# DS132-1_2-B.net
KiCad netlist of a schematic drawn in Altium Designer
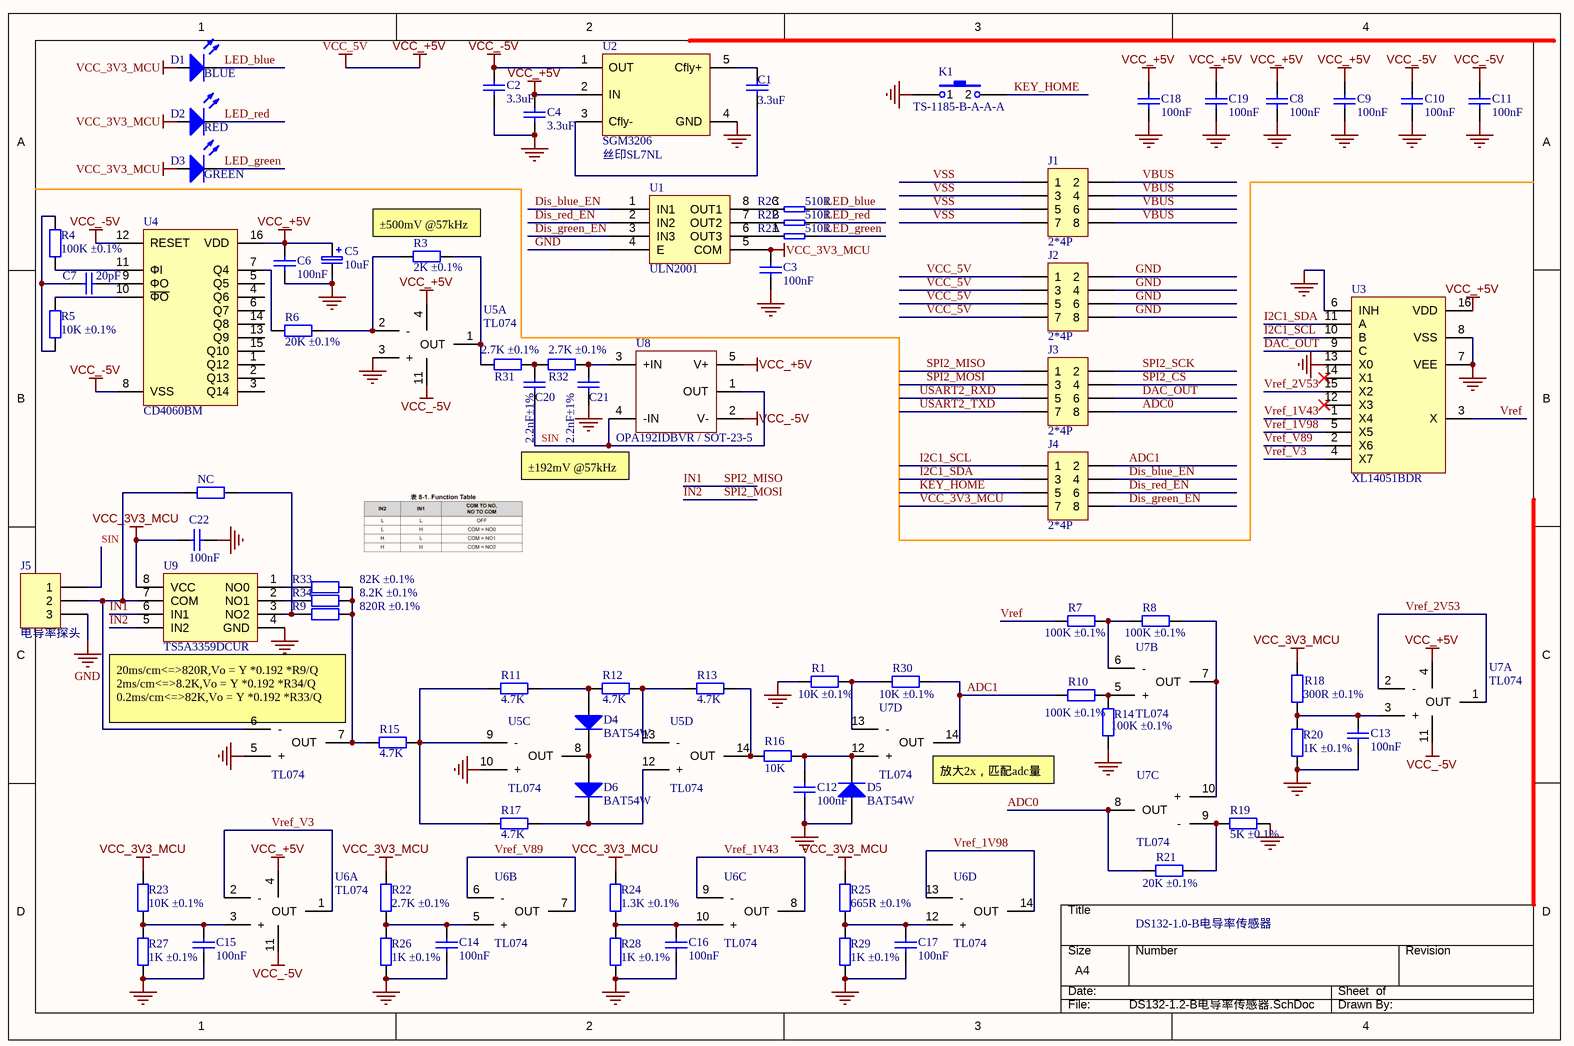
[diagram p0: DS132-1.2-B电导率传感器.SchDoc]

(export (version "E")
  (design (tool "Eeschema 10.0.6"))
  (components
    (comp (ref "C1")
      (value "3.3uF")
      (footprint "0603CAP")
      (description "贴片电容")
      (fields (field (name "Comment") "MLCC 3.3uF 50V ±10％ 0603"))
      (libsource (lib "AD_SCH") (part "MLCC 3.3uF 50V ±10％ 0603"))
    )
    (comp (ref "C2")
      (value "3.3uF")
      (footprint "0603CAP")
      (description "贴片电容")
      (libsource (lib "AD_SCH") (part "MLCC 3.3uF 50V ±10％ 0603"))
    )
    (comp (ref "C3")
      (value "100nF")
      (footprint "0603CAP")
      (description "贴片电容")
      (libsource (lib "AD_SCH") (part "MLCC 100nF 50V ±10％ 0603"))
    )
    (comp (ref "C4")
      (value "3.3uF")
      (footprint "0603CAP")
      (description "贴片电容")
      (fields (field (name "Comment") "MLCC 3.3uF 50V ±10％ 0603"))
      (libsource (lib "AD_SCH") (part "MLCC 3.3uF 50V ±10％ 0603"))
    )
    (comp (ref "C5")
      (value "10uF")
      (footprint "AVX_3216-18(1206)_SMD")
      (description "钽电容")
      (fields (field (name "Comment") "AVX_10uF/16V ±10％(C106)"))
      (libsource (lib "AD_SCH") (part "AVX_10uF/16V ±10％(C106)"))
    )
    (comp (ref "C6")
      (value "100nF")
      (footprint "0603CAP")
      (description "贴片电容")
      (fields (field (name "Comment") "SMDCAP00013"))
      (libsource (lib "AD_SCH") (part "MLCC 100nF 50V ±10％ 0603"))
    )
    (comp (ref "C7")
      (value "20pF")
      (footprint "0603CAP")
      (description "贴片电容")
      (fields (field (name "Comment") "SMDCAP00002"))
      (libsource (lib "AD_SCH") (part "MLCC 20pF 50V ±10％ 0603"))
    )
    (comp (ref "C8")
      (value "100nF")
      (footprint "0603CAP")
      (description "贴片电容")
      (libsource (lib "AD_SCH") (part "MLCC 100nF 50V ±10％ 0603"))
    )
    (comp (ref "C9")
      (value "100nF")
      (footprint "0603CAP")
      (description "贴片电容")
      (libsource (lib "AD_SCH") (part "MLCC 100nF 50V ±10％ 0603"))
    )
    (comp (ref "C10")
      (value "100nF")
      (footprint "0603CAP")
      (description "贴片电容")
      (libsource (lib "AD_SCH") (part "MLCC 100nF 50V ±10％ 0603"))
    )
    (comp (ref "C11")
      (value "100nF")
      (footprint "0603CAP")
      (description "贴片电容")
      (libsource (lib "AD_SCH") (part "MLCC 100nF 50V ±10％ 0603"))
    )
    (comp (ref "C12")
      (value "100nF")
      (footprint "0603CAP")
      (description "贴片电容")
      (libsource (lib "AD_SCH") (part "MLCC 100nF 50V ±10％ 0603"))
    )
    (comp (ref "C13")
      (value "100nF")
      (footprint "0603CAP")
      (description "贴片电容")
      (libsource (lib "AD_SCH") (part "MLCC 100nF 50V ±10％ 0603"))
    )
    (comp (ref "C14")
      (value "100nF")
      (footprint "0603CAP")
      (description "贴片电容")
      (libsource (lib "AD_SCH") (part "MLCC 100nF 50V ±10％ 0603"))
    )
    (comp (ref "C15")
      (value "100nF")
      (footprint "0603CAP")
      (description "贴片电容")
      (libsource (lib "AD_SCH") (part "MLCC 100nF 50V ±10％ 0603"))
    )
    (comp (ref "C16")
      (value "100nF")
      (footprint "0603CAP")
      (description "贴片电容")
      (libsource (lib "AD_SCH") (part "MLCC 100nF 50V ±10％ 0603"))
    )
    (comp (ref "C17")
      (value "100nF")
      (footprint "0603CAP")
      (description "贴片电容")
      (libsource (lib "AD_SCH") (part "MLCC 100nF 50V ±10％ 0603"))
    )
    (comp (ref "C18")
      (value "100nF")
      (footprint "0603CAP")
      (description "贴片电容")
      (libsource (lib "AD_SCH") (part "MLCC 100nF 50V ±10％ 0603"))
    )
    (comp (ref "C19")
      (value "100nF")
      (footprint "0603CAP")
      (description "贴片电容")
      (libsource (lib "AD_SCH") (part "MLCC 100nF 50V ±10％ 0603"))
    )
    (comp (ref "C20")
      (value "2.2nF±1%")
      (footprint "0603CAP")
      (description "贴片电容")
      (fields (field (name "Comment") "MLCC 2.2nF 50V ±1％ 0603"))
      (libsource (lib "AD_SCH") (part "MLCC 2.2nF 50V ±1％ 0603"))
    )
    (comp (ref "C21")
      (value "2.2nF±1%")
      (footprint "0603CAP")
      (description "贴片电容")
      (fields (field (name "Comment") "MLCC 2.2nF 50V ±1％ 0603"))
      (libsource (lib "AD_SCH") (part "MLCC 2.2nF 50V ±1％ 0603"))
    )
    (comp (ref "C22")
      (value "100nF")
      (footprint "0603CAP")
      (description "贴片电容")
      (libsource (lib "AD_SCH") (part "MLCC 100nF 50V ±10％ 0603"))
    )
    (comp (ref "D1")
      (value "BLUE")
      (footprint "LED_0805")
      (description "贴片LED")
      (fields (field (name "Comment") "SMDLED00010"))
      (libsource (lib "AD_SCH") (part "Chip 蓝色LED 0805"))
    )
    (comp (ref "D2")
      (value "RED")
      (footprint "LED_0805")
      (description "贴片LED")
      (fields (field (name "Comment") "SMDLED00003"))
      (libsource (lib "AD_SCH") (part "Chip 红色LED 0805"))
    )
    (comp (ref "D3")
      (value "GREEN")
      (footprint "LED_0805")
      (description "贴片LED")
      (fields (field (name "Comment") "Chip 翠绿LED 0805"))
      (libsource (lib "AD_SCH") (part "Chip 翠绿LED 0805"))
    )
    (comp (ref "D4") (value "BAT54W") (footprint "SOD-123") (libsource (lib "AD_SCH") (part "BAT54W")))
    (comp (ref "D5") (value "BAT54W") (footprint "SOD-123") (libsource (lib "AD_SCH") (part "BAT54W")))
    (comp (ref "D6") (value "BAT54W") (footprint "SOD-123") (libsource (lib "AD_SCH") (part "BAT54W")))
    (comp (ref "J1")
      (value "2*4P")
      (footprint "X1321WVS-2x04J-C40D53")
      (description "双排针2x4P 立贴 1.27mm")
      (fields (field (name "Comment") "X1321WVS-2x04J-C40D53"))
      (libsource (lib "AD_SCH") (part "X1321WVS-2x04J-C40D53"))
    )
    (comp (ref "J2")
      (value "2*4P")
      (footprint "X1321WVS-2x04J-C40D53")
      (description "双排针2x4P 立贴 1.27mm")
      (fields (field (name "Comment") "X1321WVS-2x04J-C40D53"))
      (libsource (lib "AD_SCH") (part "X1321WVS-2x04J-C40D53"))
    )
    (comp (ref "J3")
      (value "2*4P")
      (footprint "X1321WVS-2x04J-C40D53")
      (description "双排针2x4P 立贴 1.27mm")
      (fields (field (name "Comment") "X1321WVS-2x04J-C40D53"))
      (libsource (lib "AD_SCH") (part "X1321WVS-2x04J-C40D53"))
    )
    (comp (ref "J4")
      (value "2*4P")
      (footprint "X1321WVS-2x04J-C40D53")
      (description "双排针2x4P 立贴 1.27mm")
      (fields (field (name "Comment") "X1321WVS-2x04J-C40D53"))
      (libsource (lib "AD_SCH") (part "X1321WVS-2x04J-C40D53"))
    )
    (comp (ref "J5")
      (value "电导率探头")
      (footprint "SIP3")
      (description "单排直针")
      (fields (field (name "Comment") "SL000000042"))
      (libsource (lib "AD_SCH") (part "DIP3 单排直针 间距2.54mm 针长11mm 铜"))
    )
    (comp (ref "K1")
      (value "TS-1185-B-A-A-A")
      (footprint "KEY_TS-1185-x-A-A-A")
      (description "轻触开关")
      (libsource (lib "AD_SCH") (part "TS-1185-B-A-A-A"))
    )
    (comp (ref "NC")
      (value "Chip 0R 1/16W ±1％ 0603")
      (footprint "0603RES")
      (description "贴片电阻")
      (libsource (lib "AD_SCH") (part "Chip 0R 1/16W ±1％ 0603"))
    )
    (comp (ref "R1")
      (value "10K ±0.1%")
      (footprint "0603RES")
      (fields (field (name "Comment") "Chip 10K 1/10W ±0.1％ 0603"))
      (libsource (lib "") (part "Chip 10K 1/10W ±0.1％ 0603_1"))
    )
    (comp (ref "R2")
      (value "510R")
      (footprint "0603RES_Pack4")
      (description "贴片排阻")
      (fields (field (name "Comment") "SMDRES05003"))
      (libsource (lib "AD_SCH") (part "Chip R*4 510R 1/16W ±5％ 0603"))
    )
    (comp (ref "R3")
      (value "2K ±0.1%")
      (footprint "0603RES")
      (fields (field (name "Comment") "Chip 2K 1/10W ±0.1％ 0603"))
      (libsource (lib "AD_SCH") (part "Chip 2K 1/10W ±0.1％ 0603"))
    )
    (comp (ref "R4")
      (value "100K ±0.1%")
      (footprint "0603RES")
      (libsource (lib "") (part "Chip 100K 1/10W ±0.1％ 0603_1"))
    )
    (comp (ref "R5")
      (value "10K ±0.1%")
      (footprint "0603RES")
      (fields (field (name "Comment") "Chip 10K 1/10W ±0.1％ 0603"))
      (libsource (lib "AD_SCH") (part "Chip 10K 1/10W ±0.1％ 0603"))
    )
    (comp (ref "R6")
      (value "20K ±0.1%")
      (footprint "0603RES")
      (fields (field (name "Comment") "Chip 20K 1/10W ±0.1％ 0603"))
      (libsource (lib "AD_SCH") (part "Chip 20K 1/10W ±0.1％ 0603"))
    )
    (comp (ref "R7")
      (value "100K ±0.1%")
      (footprint "0603RES")
      (fields (field (name "Comment") "Chip 100K 1/10W ±0.1％ 0603"))
      (libsource (lib "") (part "Chip 100K 1/10W ±0.1％ 0603_2"))
    )
    (comp (ref "R8")
      (value "100K ±0.1%")
      (footprint "0603RES")
      (fields (field (name "Comment") "Chip 100K 1/10W ±0.1％ 0603"))
      (libsource (lib "AD_SCH") (part "Chip 100K 1/10W ±0.1％ 0603"))
    )
    (comp (ref "R9")
      (value "820R ±0.1%")
      (footprint "0603RES")
      (fields (field (name "Comment") "Chip 820R 1/10W ±0.1％ 0603"))
      (libsource (lib "AD_SCH") (part "Chip 820R 1/10W ±0.1％ 0603"))
    )
    (comp (ref "R10")
      (value "100K ±0.1%")
      (footprint "0603RES")
      (fields (field (name "Comment") "Chip 100K 1/10W ±0.1％ 0603"))
      (libsource (lib "") (part "Chip 100K 1/10W ±0.1％ 0603_2"))
    )
    (comp (ref "R11")
      (value "4.7K")
      (footprint "0603RES")
      (description "贴片电阻")
      (fields (field (name "Comment") "SMDRES00047"))
      (libsource (lib "AD_SCH") (part "Chip 4.7K 1/10W ±1％ 0603"))
    )
    (comp (ref "R12")
      (value "4.7K")
      (footprint "0603RES")
      (description "贴片电阻")
      (fields (field (name "Comment") "SMDRES00047"))
      (libsource (lib "AD_SCH") (part "Chip 4.7K 1/10W ±1％ 0603"))
    )
    (comp (ref "R13")
      (value "4.7K")
      (footprint "0603RES")
      (description "贴片电阻")
      (fields (field (name "Comment") "SMDRES00047"))
      (libsource (lib "AD_SCH") (part "Chip 4.7K 1/10W ±1％ 0603"))
    )
    (comp (ref "R14")
      (value "100K ±0.1%")
      (footprint "0603RES")
      (fields (field (name "Comment") "Chip 100K 1/10W ±0.1％ 0603"))
      (libsource (lib "") (part "Chip 100K 1/10W ±0.1％ 0603_1"))
    )
    (comp (ref "R15")
      (value "4.7K")
      (footprint "0603RES")
      (description "贴片电阻")
      (fields (field (name "Comment") "SMDRES00047"))
      (libsource (lib "AD_SCH") (part "Chip 4.7K 1/10W ±1％ 0603"))
    )
    (comp (ref "R16")
      (value "10K")
      (footprint "0603RES")
      (description "贴片电阻")
      (fields (field (name "Comment") "Chip 10K 1/16W ±1％ 0603"))
      (libsource (lib "AD_SCH") (part "Chip 10K 1/16W ±1％ 0603"))
    )
    (comp (ref "R17")
      (value "4.7K")
      (footprint "0603RES")
      (description "贴片电阻")
      (fields (field (name "Comment") "SMDRES00047"))
      (libsource (lib "AD_SCH") (part "Chip 4.7K 1/10W ±1％ 0603"))
    )
    (comp (ref "R18")
      (value "300R ±0.1%")
      (footprint "0603RES")
      (libsource (lib "AD_SCH") (part "Chip 300R 1/10W ±0.1％ 0603"))
    )
    (comp (ref "R19")
      (value "5K ±0.1%")
      (footprint "0603RES")
      (fields (field (name "Comment") "Chip 5K 1/10W ±0.1％ 0603"))
      (libsource (lib "AD_SCH") (part "Chip 5K 1/10W ±0.1％ 0603"))
    )
    (comp (ref "R20")
      (value "1K ±0.1%")
      (footprint "0603RES")
      (fields (field (name "Comment") "Chip 1K 1/10W ±0.1％ 0603"))
      (libsource (lib "AD_SCH") (part "Chip 1K 1/10W ±0.1％ 0603"))
    )
    (comp (ref "R21")
      (value "20K ±0.1%")
      (footprint "0603RES")
      (fields (field (name "Comment") "Chip 20K 1/10W ±0.1％ 0603"))
      (libsource (lib "AD_SCH") (part "Chip 20K 1/10W ±0.1％ 0603"))
    )
    (comp (ref "R22")
      (value "2.7K ±0.1%")
      (footprint "0603RES")
      (fields (field (name "Comment") "Chip 2.7K 1/10W ±0.1％ 0603"))
      (libsource (lib "") (part "Chip 2.7K 1/10W ±0.1％ 0603_1"))
    )
    (comp (ref "R23")
      (value "10K ±0.1%")
      (footprint "0603RES")
      (fields (field (name "Comment") "Chip 10K 1/10W ±0.1％ 0603"))
      (libsource (lib "AD_SCH") (part "Chip 10K 1/10W ±0.1％ 0603"))
    )
    (comp (ref "R24")
      (value "1.3K ±0.1%")
      (footprint "0603RES")
      (fields (field (name "Comment") "Chip 1.3K 1/10W ±0.1％ 0603"))
      (libsource (lib "AD_SCH") (part "Chip 1.3K 1/10W ±0.1％ 0603"))
    )
    (comp (ref "R25")
      (value "665R ±0.1%")
      (footprint "0603RES")
      (fields (field (name "Comment") "Chip 665R 1/10W ±0.1％ 0603"))
      (libsource (lib "AD_SCH") (part "Chip 665R 1/10W ±0.1％ 0603"))
    )
    (comp (ref "R26")
      (value "1K ±0.1%")
      (footprint "0603RES")
      (fields (field (name "Comment") "Chip 1K 1/10W ±0.1％ 0603"))
      (libsource (lib "AD_SCH") (part "Chip 1K 1/10W ±0.1％ 0603"))
    )
    (comp (ref "R27")
      (value "1K ±0.1%")
      (footprint "0603RES")
      (fields (field (name "Comment") "Chip 1K 1/10W ±0.1％ 0603"))
      (libsource (lib "AD_SCH") (part "Chip 1K 1/10W ±0.1％ 0603"))
    )
    (comp (ref "R28")
      (value "1K ±0.1%")
      (footprint "0603RES")
      (fields (field (name "Comment") "Chip 1K 1/10W ±0.1％ 0603"))
      (libsource (lib "AD_SCH") (part "Chip 1K 1/10W ±0.1％ 0603"))
    )
    (comp (ref "R29")
      (value "1K ±0.1%")
      (footprint "0603RES")
      (fields (field (name "Comment") "Chip 1K 1/10W ±0.1％ 0603"))
      (libsource (lib "AD_SCH") (part "Chip 1K 1/10W ±0.1％ 0603"))
    )
    (comp (ref "R30")
      (value "10K ±0.1%")
      (footprint "0603RES")
      (fields (field (name "Comment") "Chip 10K 1/10W ±0.1％ 0603"))
      (libsource (lib "") (part "Chip 10K 1/10W ±0.1％ 0603_1"))
    )
    (comp (ref "R31")
      (value "2.7K ±0.1%")
      (footprint "0603RES")
      (fields (field (name "Comment") "Chip 2.7K 1/10W ±0.1％ 0603"))
      (libsource (lib "AD_SCH") (part "Chip 2.7K 1/10W ±0.1％ 0603"))
    )
    (comp (ref "R32")
      (value "2.7K ±0.1%")
      (footprint "0603RES")
      (fields (field (name "Comment") "Chip 2.7K 1/10W ±0.1％ 0603"))
      (libsource (lib "AD_SCH") (part "Chip 2.7K 1/10W ±0.1％ 0603"))
    )
    (comp (ref "R33")
      (value "82K ±0.1%")
      (footprint "0603RES")
      (fields (field (name "Comment") "SMDRES00096"))
      (libsource (lib "AD_SCH") (part "Chip 82K 1/10W ±0.1％ 0603"))
    )
    (comp (ref "R34")
      (value "8.2K ±0.1%")
      (footprint "0603RES")
      (fields (field (name "Comment") "Chip 8.2k 1/10W ±0.1％ 0603"))
      (libsource (lib "AD_SCH") (part "Chip 8.2k 1/10W ±0.1％ 0603"))
    )
    (comp (ref "U1")
      (value "ULN2001")
      (footprint "SO-8")
      (description "电机驱动芯片")
      (fields (field (name "Comment") "SMDIC000018"))
      (libsource (lib "AD_SCH") (part "ULN2001 SOP-8"))
    )
    (comp (ref "U2")
      (value "SGM3206")
      (footprint "SOT23-5")
      (description "电荷泵芯片")
      (fields (field (name "ALTIUM_VALUE") "丝印SL7NL"))
      (libsource (lib "AD_SCH") (part "SGM3206"))
    )
    (comp (ref "U3")
      (value "XL14051BDR")
      (footprint "SO-16")
      (description "XINLUDA(信路达)\r\nXL14051BDR\r\nSOP-16​")
      (libsource (lib "AD_SCH") (part "XL14051BDR"))
    )
    (comp (ref "U4")
      (value "CD4060BM")
      (footprint "SO-16")
      (description "HGSEMI(华冠)\r\nCD4060BM/TR\r\nSOP-16")
      (libsource (lib "AD_SCH") (part "CD4060BM"))
    )
    (comp (ref "U5")
      (value "TL074")
      (footprint "SO-14")
      (description "TI\r\nTL074CDR\r\nSOIC-14")
      (libsource (lib "AD_SCH") (part "TL074"))
    )
    (comp (ref "U6")
      (value "TL074")
      (footprint "SO-14")
      (description "TI\r\nTL074CDR\r\nSOIC-14")
      (libsource (lib "AD_SCH") (part "TL074"))
    )
    (comp (ref "U7")
      (value "TL074")
      (footprint "SO-14")
      (description "TI\r\nTL074CDR\r\nSOIC-14")
      (libsource (lib "AD_SCH") (part "TL074"))
    )
    (comp (ref "U8")
      (value "OPA192IDBVR / SOT-23-5")
      (footprint "SOT23-5")
      (description "低失调电压: 65 µV（最大值）\r\n低输入偏置电流: 1 pA（最大值）\r\n单电源供电：2.7 V至5.5 V")
      (libsource (lib "AD_SCH") (part "AD8605"))
    )
    (comp (ref "U9")
      (value "TS5A3359DCUR")
      (footprint "VSSOP-8")
      (description "单刀三掷(SP3T)模拟开关")
      (libsource (lib "AD_SCH") (part "TS5A3359DCUR"))
    )
  )
  (nets
    (net (code "1") (name "/ADC0") (class "Default")
      (node (ref "J3") (pin "8") (pinfunction "8_8") (pintype "passive"))
      (node (ref "R21") (pin "1") (pinfunction "1_1") (pintype "passive"))
      (node (ref "U7") (pin "8") (pinfunction "OUT_8") (pintype "passive"))
    )
    (net (code "2") (name "/ADC1") (class "Default")
      (node (ref "J4") (pin "2") (pinfunction "2_2") (pintype "passive"))
      (node (ref "R10") (pin "1") (pinfunction "1_1") (pintype "passive"))
      (node (ref "R30") (pin "2") (pinfunction "2_2") (pintype "passive"))
      (node (ref "U7") (pin "14") (pinfunction "OUT_14") (pintype "passive"))
    )
    (net (code "3") (name "/DAC_OUT") (class "Default")
      (node (ref "J3") (pin "6") (pinfunction "6_6") (pintype "passive"))
      (node (ref "U3") (pin "9") (pinfunction "C_9") (pintype "passive"))
    )
    (net (code "4") (name "/Dis_blue_EN") (class "Default")
      (node (ref "J4") (pin "4") (pinfunction "4_4") (pintype "passive"))
      (node (ref "U1") (pin "1") (pinfunction "IN1_1") (pintype "passive"))
    )
    (net (code "5") (name "/Dis_green_EN") (class "Default")
      (node (ref "J4") (pin "8") (pinfunction "8_8") (pintype "passive"))
      (node (ref "U1") (pin "3") (pinfunction "IN3_3") (pintype "passive"))
    )
    (net (code "6") (name "/Dis_red_EN") (class "Default")
      (node (ref "J4") (pin "6") (pinfunction "6_6") (pintype "passive"))
      (node (ref "U1") (pin "2") (pinfunction "IN2_2") (pintype "passive"))
    )
    (net (code "7") (name "/I2C1_SCL") (class "Default")
      (node (ref "J4") (pin "1") (pinfunction "1_1") (pintype "passive"))
      (node (ref "U3") (pin "10") (pinfunction "B_10") (pintype "passive"))
    )
    (net (code "8") (name "/I2C1_SDA") (class "Default")
      (node (ref "J4") (pin "3") (pinfunction "3_3") (pintype "passive"))
      (node (ref "U3") (pin "11") (pinfunction "A_11") (pintype "passive"))
    )
    (net (code "9") (name "/IN1") (class "Default")
      (node (ref "J3") (pin "1") (pinfunction "1_1") (pintype "passive"))
      (node (ref "U9") (pin "6") (pinfunction "IN1_6") (pintype "passive"))
    )
    (net (code "10") (name "/IN2") (class "Default")
      (node (ref "J3") (pin "3") (pinfunction "3_3") (pintype "passive"))
      (node (ref "U9") (pin "5") (pinfunction "IN2_5") (pintype "passive"))
    )
    (net (code "11") (name "/KEY_HOME") (class "Default")
      (node (ref "J4") (pin "5") (pinfunction "5_5") (pintype "passive"))
      (node (ref "K1") (pin "2") (pinfunction "2_2") (pintype "passive"))
    )
    (net (code "12") (name "/LED_blue") (class "Default")
      (node (ref "D1") (pin "2") (pinfunction "K_2") (pintype "passive"))
      (node (ref "R2") (pin "6") (pinfunction "6_6") (pintype "passive"))
    )
    (net (code "13") (name "/LED_green") (class "Default")
      (node (ref "D3") (pin "2") (pinfunction "K_2") (pintype "passive"))
      (node (ref "R2") (pin "8") (pinfunction "8_8") (pintype "passive"))
    )
    (net (code "14") (name "/LED_red") (class "Default")
      (node (ref "D2") (pin "2") (pinfunction "K_2") (pintype "passive"))
      (node (ref "R2") (pin "7") (pinfunction "7_7") (pintype "passive"))
    )
    (net (code "15") (name "/SIN") (class "Default")
      (node (ref "C20") (pin "1") (pinfunction "1_1") (pintype "passive"))
      (node (ref "J5") (pin "1") (pinfunction "1_1") (pintype "passive"))
      (node (ref "U8") (pin "1") (pinfunction "OUT_1") (pintype "passive"))
      (node (ref "U8") (pin "4") (pinfunction "-IN_4") (pintype "passive"))
    )
    (net (code "16") (name "/SPI2_CS") (class "Default")
      (node (ref "J3") (pin "4") (pinfunction "4_4") (pintype "passive"))
    )
    (net (code "17") (name "/SPI2_SCK") (class "Default")
      (node (ref "J3") (pin "2") (pinfunction "2_2") (pintype "passive"))
    )
    (net (code "18") (name "/USART2_RXD") (class "Default")
      (node (ref "J3") (pin "5") (pinfunction "5_5") (pintype "passive"))
    )
    (net (code "19") (name "/USART2_TXD") (class "Default")
      (node (ref "J3") (pin "7") (pinfunction "7_7") (pintype "passive"))
    )
    (net (code "20") (name "/VBUS") (class "Default")
      (node (ref "J1") (pin "2") (pinfunction "2_2") (pintype "passive"))
      (node (ref "J1") (pin "4") (pinfunction "4_4") (pintype "passive"))
      (node (ref "J1") (pin "6") (pinfunction "6_6") (pintype "passive"))
      (node (ref "J1") (pin "8") (pinfunction "8_8") (pintype "passive"))
    )
    (net (code "21") (name "/VSS") (class "Default")
      (node (ref "J1") (pin "1") (pinfunction "1_1") (pintype "passive"))
      (node (ref "J1") (pin "3") (pinfunction "3_3") (pintype "passive"))
      (node (ref "J1") (pin "5") (pinfunction "5_5") (pintype "passive"))
      (node (ref "J1") (pin "7") (pinfunction "7_7") (pintype "passive"))
    )
    (net (code "22") (name "/Vref") (class "Default")
      (node (ref "R7") (pin "1") (pinfunction "1_1") (pintype "passive"))
      (node (ref "U3") (pin "3") (pinfunction "X_3") (pintype "passive"))
    )
    (net (code "23") (name "/Vref_1V43") (class "Default")
      (node (ref "U3") (pin "1") (pinfunction "X4_1") (pintype "passive"))
      (node (ref "U6") (pin "8") (pinfunction "OUT_8") (pintype "passive"))
      (node (ref "U6") (pin "9") (pinfunction "-_9") (pintype "passive"))
    )
    (net (code "24") (name "/Vref_1V98") (class "Default")
      (node (ref "U3") (pin "5") (pinfunction "X5_5") (pintype "passive"))
      (node (ref "U6") (pin "13") (pinfunction "-_13") (pintype "passive"))
      (node (ref "U6") (pin "14") (pinfunction "OUT_14") (pintype "passive"))
    )
    (net (code "25") (name "/Vref_2V53") (class "Default")
      (node (ref "U3") (pin "15") (pinfunction "X2_15") (pintype "passive"))
      (node (ref "U7") (pin "1") (pinfunction "OUT_1") (pintype "passive"))
      (node (ref "U7") (pin "2") (pinfunction "-_2") (pintype "passive"))
    )
    (net (code "26") (name "/Vref_V3") (class "Default")
      (node (ref "U3") (pin "4") (pinfunction "X7_4") (pintype "passive"))
      (node (ref "U6") (pin "1") (pinfunction "OUT_1") (pintype "passive"))
      (node (ref "U6") (pin "2") (pinfunction "-_2") (pintype "passive"))
    )
    (net (code "27") (name "/Vref_V89") (class "Default")
      (node (ref "U3") (pin "2") (pinfunction "X6_2") (pintype "passive"))
      (node (ref "U6") (pin "6") (pinfunction "-_6") (pintype "passive"))
      (node (ref "U6") (pin "7") (pinfunction "OUT_7") (pintype "passive"))
    )
    (net (code "28") (name "GND") (class "Default")
      (node (ref "C10") (pin "1") (pinfunction "1_1") (pintype "passive"))
      (node (ref "C11") (pin "1") (pinfunction "1_1") (pintype "passive"))
      (node (ref "C12") (pin "1") (pinfunction "1_1") (pintype "passive"))
      (node (ref "C13") (pin "2") (pinfunction "2_2") (pintype "passive"))
      (node (ref "C14") (pin "2") (pinfunction "2_2") (pintype "passive"))
      (node (ref "C15") (pin "2") (pinfunction "2_2") (pintype "passive"))
      (node (ref "C16") (pin "2") (pinfunction "2_2") (pintype "passive"))
      (node (ref "C17") (pin "2") (pinfunction "2_2") (pintype "passive"))
      (node (ref "C18") (pin "1") (pinfunction "1_1") (pintype "passive"))
      (node (ref "C19") (pin "1") (pinfunction "1_1") (pintype "passive"))
      (node (ref "C2") (pin "2") (pinfunction "2_2") (pintype "passive"))
      (node (ref "C21") (pin "1") (pinfunction "1_1") (pintype "passive"))
      (node (ref "C22") (pin "2") (pinfunction "2_2") (pintype "passive"))
      (node (ref "C3") (pin "1") (pinfunction "1_1") (pintype "passive"))
      (node (ref "C4") (pin "2") (pinfunction "2_2") (pintype "passive"))
      (node (ref "C5") (pin "2") (pinfunction "2_2") (pintype "passive"))
      (node (ref "C6") (pin "2") (pinfunction "2_2") (pintype "passive"))
      (node (ref "C8") (pin "1") (pinfunction "1_1") (pintype "passive"))
      (node (ref "C9") (pin "1") (pinfunction "1_1") (pintype "passive"))
      (node (ref "D5") (pin "1") (pinfunction "A_1") (pintype "passive"))
      (node (ref "J2") (pin "2") (pinfunction "2_2") (pintype "passive"))
      (node (ref "J2") (pin "4") (pinfunction "4_4") (pintype "passive"))
      (node (ref "J2") (pin "6") (pinfunction "6_6") (pintype "passive"))
      (node (ref "J2") (pin "8") (pinfunction "8_8") (pintype "passive"))
      (node (ref "J5") (pin "3") (pinfunction "3_3") (pintype "passive"))
      (node (ref "K1") (pin "1") (pinfunction "1_1") (pintype "passive"))
      (node (ref "R1") (pin "1") (pinfunction "1_1") (pintype "passive"))
      (node (ref "R14") (pin "1") (pinfunction "1_1") (pintype "passive"))
      (node (ref "R19") (pin "2") (pinfunction "2_2") (pintype "passive"))
      (node (ref "R20") (pin "1") (pinfunction "1_1") (pintype "passive"))
      (node (ref "R26") (pin "1") (pinfunction "1_1") (pintype "passive"))
      (node (ref "R27") (pin "1") (pinfunction "1_1") (pintype "passive"))
      (node (ref "R28") (pin "1") (pinfunction "1_1") (pintype "passive"))
      (node (ref "R29") (pin "1") (pinfunction "1_1") (pintype "passive"))
      (node (ref "U1") (pin "4") (pinfunction "E_4") (pintype "passive"))
      (node (ref "U2") (pin "4") (pinfunction "GND_4") (pintype "passive"))
      (node (ref "U3") (pin "13") (pinfunction "X0_13") (pintype "passive"))
      (node (ref "U3") (pin "6") (pinfunction "INH_6") (pintype "passive"))
      (node (ref "U3") (pin "7") (pinfunction "VEE_7") (pintype "passive"))
      (node (ref "U3") (pin "8") (pinfunction "VSS_8") (pintype "passive"))
      (node (ref "U5") (pin "10") (pinfunction "+_10") (pintype "passive"))
      (node (ref "U5") (pin "3") (pinfunction "+_3") (pintype "passive"))
      (node (ref "U5") (pin "5") (pinfunction "+_5") (pintype "passive"))
      (node (ref "U9") (pin "4") (pinfunction "GND_4") (pintype "passive"))
    )
    (net (code "29") (name "Net-(C7-Pad2)") (class "Default")
      (node (ref "C7") (pin "2") (pinfunction "2_2") (pintype "passive"))
      (node (ref "R4") (pin "2") (pinfunction "2_2") (pintype "passive"))
      (node (ref "R5") (pin "1") (pinfunction "1_1") (pintype "passive"))
    )
    (net (code "30") (name "Net-(C20-Pad2)") (class "Default")
      (node (ref "C20") (pin "2") (pinfunction "2_2") (pintype "passive"))
      (node (ref "R31") (pin "2") (pinfunction "2_2") (pintype "passive"))
      (node (ref "R32") (pin "1") (pinfunction "1_1") (pintype "passive"))
    )
    (net (code "31") (name "Net-(D4-A)") (class "Default")
      (node (ref "D4") (pin "1") (pinfunction "A_1") (pintype "passive"))
      (node (ref "R11") (pin "2") (pinfunction "2_2") (pintype "passive"))
      (node (ref "R12") (pin "1") (pinfunction "1_1") (pintype "passive"))
    )
    (net (code "32") (name "Net-(D4-K)") (class "Default")
      (node (ref "D4") (pin "2") (pinfunction "K_2") (pintype "passive"))
      (node (ref "D6") (pin "1") (pinfunction "A_1") (pintype "passive"))
      (node (ref "U5") (pin "8") (pinfunction "OUT_8") (pintype "passive"))
    )
    (net (code "33") (name "Net-(D5-K)") (class "Default")
      (node (ref "C12") (pin "2") (pinfunction "2_2") (pintype "passive"))
      (node (ref "D5") (pin "2") (pinfunction "K_2") (pintype "passive"))
      (node (ref "R16") (pin "2") (pinfunction "2_2") (pintype "passive"))
      (node (ref "U7") (pin "12") (pinfunction "+_12") (pintype "passive"))
    )
    (net (code "34") (name "Net-(D6-K)") (class "Default")
      (node (ref "D6") (pin "2") (pinfunction "K_2") (pintype "passive"))
      (node (ref "R17") (pin "2") (pinfunction "2_2") (pintype "passive"))
      (node (ref "U5") (pin "12") (pinfunction "+_12") (pintype "passive"))
    )
    (net (code "35") (name "Net-(U1-OUT1)") (class "Default")
      (node (ref "R2") (pin "3") (pinfunction "3_3") (pintype "passive"))
      (node (ref "U1") (pin "8") (pinfunction "OUT1_8") (pintype "passive"))
    )
    (net (code "36") (name "Net-(U1-OUT2)") (class "Default")
      (node (ref "R2") (pin "2") (pinfunction "2_2") (pintype "passive"))
      (node (ref "U1") (pin "7") (pinfunction "OUT2_7") (pintype "passive"))
    )
    (net (code "37") (name "Net-(U1-OUT3)") (class "Default")
      (node (ref "R2") (pin "1") (pinfunction "1_1") (pintype "passive"))
      (node (ref "U1") (pin "6") (pinfunction "OUT3_6") (pintype "passive"))
    )
    (net (code "38") (name "Net-(U2-Cfly+)") (class "Default")
      (node (ref "C1") (pin "2") (pinfunction "2_2") (pintype "passive"))
      (node (ref "U2") (pin "5") (pinfunction "Cfly+_5") (pintype "passive"))
    )
    (net (code "39") (name "Net-(U2-Cfly-)") (class "Default")
      (node (ref "C1") (pin "1") (pinfunction "1_1") (pintype "passive"))
      (node (ref "U2") (pin "3") (pinfunction "Cfly-_3") (pintype "passive"))
    )
    (net (code "40") (name "Net-(U4-Q4)") (class "Default")
      (node (ref "R6") (pin "1") (pinfunction "1_1") (pintype "passive"))
      (node (ref "U4") (pin "7") (pinfunction "Q4_7") (pintype "passive"))
    )
    (net (code "41") (name "Net-(U4-~{ΦO})") (class "Default")
      (node (ref "R5") (pin "2") (pinfunction "2_2") (pintype "passive"))
      (node (ref "U4") (pin "10") (pinfunction "~{ΦO}_10") (pintype "passive"))
    )
    (net (code "42") (name "Net-(U4-ΦI)") (class "Default")
      (node (ref "R4") (pin "1") (pinfunction "1_1") (pintype "passive"))
      (node (ref "U4") (pin "11") (pinfunction "ΦI_11") (pintype "passive"))
    )
    (net (code "43") (name "Net-(U4-ΦO)") (class "Default")
      (node (ref "C7") (pin "1") (pinfunction "1_1") (pintype "passive"))
      (node (ref "U4") (pin "9") (pinfunction "ΦO_9") (pintype "passive"))
    )
    (net (code "44") (name "Net-(U5A--)") (class "Default")
      (node (ref "R3") (pin "1") (pinfunction "1_1") (pintype "passive"))
      (node (ref "R6") (pin "2") (pinfunction "2_2") (pintype "passive"))
      (node (ref "U5") (pin "2") (pinfunction "-_2") (pintype "passive"))
    )
    (net (code "45") (name "Net-(U5A-OUT)") (class "Default")
      (node (ref "R3") (pin "2") (pinfunction "2_2") (pintype "passive"))
      (node (ref "R31") (pin "1") (pinfunction "1_1") (pintype "passive"))
      (node (ref "U5") (pin "1") (pinfunction "OUT_1") (pintype "passive"))
    )
    (net (code "46") (name "Net-(U5B--)") (class "Default")
      (node (ref "J5") (pin "2") (pinfunction "2_2") (pintype "passive"))
      (node (ref "NC") (pin "1") (pinfunction "1_1") (pintype "passive"))
      (node (ref "U5") (pin "6") (pinfunction "-_6") (pintype "passive"))
      (node (ref "U9") (pin "7") (pinfunction "COM_7") (pintype "passive"))
    )
    (net (code "47") (name "Net-(U5B-OUT)") (class "Default")
      (node (ref "R15") (pin "1") (pinfunction "1_1") (pintype "passive"))
      (node (ref "R33") (pin "2") (pinfunction "2_2") (pintype "passive"))
      (node (ref "R34") (pin "2") (pinfunction "2_2") (pintype "passive"))
      (node (ref "R9") (pin "2") (pinfunction "2_2") (pintype "passive"))
      (node (ref "U5") (pin "7") (pinfunction "OUT_7") (pintype "passive"))
    )
    (net (code "48") (name "Net-(U5C--)") (class "Default")
      (node (ref "R11") (pin "1") (pinfunction "1_1") (pintype "passive"))
      (node (ref "R15") (pin "2") (pinfunction "2_2") (pintype "passive"))
      (node (ref "R17") (pin "1") (pinfunction "1_1") (pintype "passive"))
      (node (ref "U5") (pin "9") (pinfunction "-_9") (pintype "passive"))
    )
    (net (code "49") (name "Net-(U5D--)") (class "Default")
      (node (ref "R12") (pin "2") (pinfunction "2_2") (pintype "passive"))
      (node (ref "R13") (pin "1") (pinfunction "1_1") (pintype "passive"))
      (node (ref "U5") (pin "13") (pinfunction "-_13") (pintype "passive"))
    )
    (net (code "50") (name "Net-(U5D-OUT)") (class "Default")
      (node (ref "R13") (pin "2") (pinfunction "2_2") (pintype "passive"))
      (node (ref "R16") (pin "1") (pinfunction "1_1") (pintype "passive"))
      (node (ref "U5") (pin "14") (pinfunction "OUT_14") (pintype "passive"))
    )
    (net (code "51") (name "Net-(U6A-+)") (class "Default")
      (node (ref "C15") (pin "1") (pinfunction "1_1") (pintype "passive"))
      (node (ref "R23") (pin "1") (pinfunction "1_1") (pintype "passive"))
      (node (ref "R27") (pin "2") (pinfunction "2_2") (pintype "passive"))
      (node (ref "U6") (pin "3") (pinfunction "+_3") (pintype "passive"))
    )
    (net (code "52") (name "Net-(U6B-+)") (class "Default")
      (node (ref "C14") (pin "1") (pinfunction "1_1") (pintype "passive"))
      (node (ref "R22") (pin "1") (pinfunction "1_1") (pintype "passive"))
      (node (ref "R26") (pin "2") (pinfunction "2_2") (pintype "passive"))
      (node (ref "U6") (pin "5") (pinfunction "+_5") (pintype "passive"))
    )
    (net (code "53") (name "Net-(U6C-+)") (class "Default")
      (node (ref "C16") (pin "1") (pinfunction "1_1") (pintype "passive"))
      (node (ref "R24") (pin "1") (pinfunction "1_1") (pintype "passive"))
      (node (ref "R28") (pin "2") (pinfunction "2_2") (pintype "passive"))
      (node (ref "U6") (pin "10") (pinfunction "+_10") (pintype "passive"))
    )
    (net (code "54") (name "Net-(U6D-+)") (class "Default")
      (node (ref "C17") (pin "1") (pinfunction "1_1") (pintype "passive"))
      (node (ref "R25") (pin "1") (pinfunction "1_1") (pintype "passive"))
      (node (ref "R29") (pin "2") (pinfunction "2_2") (pintype "passive"))
      (node (ref "U6") (pin "12") (pinfunction "+_12") (pintype "passive"))
    )
    (net (code "55") (name "Net-(U7A-+)") (class "Default")
      (node (ref "C13") (pin "1") (pinfunction "1_1") (pintype "passive"))
      (node (ref "R18") (pin "1") (pinfunction "1_1") (pintype "passive"))
      (node (ref "R20") (pin "2") (pinfunction "2_2") (pintype "passive"))
      (node (ref "U7") (pin "3") (pinfunction "+_3") (pintype "passive"))
    )
    (net (code "56") (name "Net-(U7B-+)") (class "Default")
      (node (ref "R10") (pin "2") (pinfunction "2_2") (pintype "passive"))
      (node (ref "R14") (pin "2") (pinfunction "2_2") (pintype "passive"))
      (node (ref "U7") (pin "5") (pinfunction "+_5") (pintype "passive"))
    )
    (net (code "57") (name "Net-(U7B--)") (class "Default")
      (node (ref "R7") (pin "2") (pinfunction "2_2") (pintype "passive"))
      (node (ref "R8") (pin "2") (pinfunction "2_2") (pintype "passive"))
      (node (ref "U7") (pin "6") (pinfunction "-_6") (pintype "passive"))
    )
    (net (code "58") (name "Net-(U7B-OUT)") (class "Default")
      (node (ref "R8") (pin "1") (pinfunction "1_1") (pintype "passive"))
      (node (ref "U7") (pin "10") (pinfunction "+_10") (pintype "passive"))
      (node (ref "U7") (pin "7") (pinfunction "OUT_7") (pintype "passive"))
    )
    (net (code "59") (name "Net-(U7C--)") (class "Default")
      (node (ref "R19") (pin "1") (pinfunction "1_1") (pintype "passive"))
      (node (ref "R21") (pin "2") (pinfunction "2_2") (pintype "passive"))
      (node (ref "U7") (pin "9") (pinfunction "-_9") (pintype "passive"))
    )
    (net (code "60") (name "Net-(U7D--)") (class "Default")
      (node (ref "R1") (pin "2") (pinfunction "2_2") (pintype "passive"))
      (node (ref "R30") (pin "1") (pinfunction "1_1") (pintype "passive"))
      (node (ref "U7") (pin "13") (pinfunction "-_13") (pintype "passive"))
    )
    (net (code "61") (name "Net-(U8-+IN)") (class "Default")
      (node (ref "C21") (pin "2") (pinfunction "2_2") (pintype "passive"))
      (node (ref "R32") (pin "2") (pinfunction "2_2") (pintype "passive"))
      (node (ref "U8") (pin "3") (pinfunction "+IN_3") (pintype "passive"))
    )
    (net (code "62") (name "Net-(U9-NO0)") (class "Default")
      (node (ref "R33") (pin "1") (pinfunction "1_1") (pintype "passive"))
      (node (ref "U9") (pin "1") (pinfunction "NO0_1") (pintype "passive"))
    )
    (net (code "63") (name "Net-(U9-NO1)") (class "Default")
      (node (ref "R34") (pin "1") (pinfunction "1_1") (pintype "passive"))
      (node (ref "U9") (pin "2") (pinfunction "NO1_2") (pintype "passive"))
    )
    (net (code "64") (name "Net-(U9-NO2)") (class "Default")
      (node (ref "NC") (pin "2") (pinfunction "2_2") (pintype "passive"))
      (node (ref "R9") (pin "1") (pinfunction "1_1") (pintype "passive"))
      (node (ref "U9") (pin "3") (pinfunction "NO2_3") (pintype "passive"))
    )
    (net (code "65") (name "VCC_+5V") (class "Default")
      (node (ref "C18") (pin "2") (pinfunction "2_2") (pintype "passive"))
      (node (ref "C19") (pin "2") (pinfunction "2_2") (pintype "passive"))
      (node (ref "C4") (pin "1") (pinfunction "1_1") (pintype "passive"))
      (node (ref "C5") (pin "1") (pinfunction "1_1") (pintype "passive"))
      (node (ref "C6") (pin "1") (pinfunction "1_1") (pintype "passive"))
      (node (ref "C8") (pin "2") (pinfunction "2_2") (pintype "passive"))
      (node (ref "C9") (pin "2") (pinfunction "2_2") (pintype "passive"))
      (node (ref "J2") (pin "1") (pinfunction "1_1") (pintype "passive"))
      (node (ref "J2") (pin "3") (pinfunction "3_3") (pintype "passive"))
      (node (ref "J2") (pin "5") (pinfunction "5_5") (pintype "passive"))
      (node (ref "J2") (pin "7") (pinfunction "7_7") (pintype "passive"))
      (node (ref "U2") (pin "2") (pinfunction "IN_2") (pintype "passive"))
      (node (ref "U3") (pin "16") (pinfunction "VDD_16") (pintype "passive"))
      (node (ref "U4") (pin "16") (pinfunction "VDD_16") (pintype "passive"))
      (node (ref "U5") (pin "4") (pinfunction "VCC_4") (pintype "passive"))
      (node (ref "U6") (pin "4") (pinfunction "VCC_4") (pintype "passive"))
      (node (ref "U7") (pin "4") (pinfunction "VCC_4") (pintype "passive"))
      (node (ref "U8") (pin "5") (pinfunction "V+_5") (pintype "passive"))
    )
    (net (code "66") (name "VCC_-5V") (class "Default")
      (node (ref "C10") (pin "2") (pinfunction "2_2") (pintype "passive"))
      (node (ref "C11") (pin "2") (pinfunction "2_2") (pintype "passive"))
      (node (ref "C2") (pin "1") (pinfunction "1_1") (pintype "passive"))
      (node (ref "U2") (pin "1") (pinfunction "OUT_1") (pintype "passive"))
      (node (ref "U4") (pin "12") (pinfunction "RESET_12") (pintype "passive"))
      (node (ref "U4") (pin "8") (pinfunction "VSS_8") (pintype "passive"))
      (node (ref "U5") (pin "11") (pinfunction "GND_11") (pintype "passive"))
      (node (ref "U6") (pin "11") (pinfunction "GND_11") (pintype "passive"))
      (node (ref "U7") (pin "11") (pinfunction "GND_11") (pintype "passive"))
      (node (ref "U8") (pin "2") (pinfunction "V-_2") (pintype "passive"))
    )
    (net (code "67") (name "VCC_3V3_MCU") (class "Default")
      (node (ref "C22") (pin "1") (pinfunction "1_1") (pintype "passive"))
      (node (ref "C3") (pin "2") (pinfunction "2_2") (pintype "passive"))
      (node (ref "D1") (pin "1") (pinfunction "A_1") (pintype "passive"))
      (node (ref "D2") (pin "1") (pinfunction "A_1") (pintype "passive"))
      (node (ref "D3") (pin "1") (pinfunction "A_1") (pintype "passive"))
      (node (ref "J4") (pin "7") (pinfunction "7_7") (pintype "passive"))
      (node (ref "R18") (pin "2") (pinfunction "2_2") (pintype "passive"))
      (node (ref "R22") (pin "2") (pinfunction "2_2") (pintype "passive"))
      (node (ref "R23") (pin "2") (pinfunction "2_2") (pintype "passive"))
      (node (ref "R24") (pin "2") (pinfunction "2_2") (pintype "passive"))
      (node (ref "R25") (pin "2") (pinfunction "2_2") (pintype "passive"))
      (node (ref "U1") (pin "5") (pinfunction "COM_5") (pintype "passive"))
      (node (ref "U9") (pin "8") (pinfunction "VCC_8") (pintype "passive"))
    )
    (net (code "68") (name "unconnected-(U3-X1-Pad14)") (class "Default")
      (node (ref "U3") (pin "14") (pinfunction "X1_14") (pintype "passive+no_connect"))
    )
    (net (code "69") (name "unconnected-(U3-X3-Pad12)") (class "Default")
      (node (ref "U3") (pin "12") (pinfunction "X3_12") (pintype "passive+no_connect"))
    )
    (net (code "70") (name "unconnected-(U4-Q5-Pad5)") (class "Default")
      (node (ref "U4") (pin "5") (pinfunction "Q5_5") (pintype "passive"))
    )
    (net (code "71") (name "unconnected-(U4-Q6-Pad4)") (class "Default")
      (node (ref "U4") (pin "4") (pinfunction "Q6_4") (pintype "passive"))
    )
    (net (code "72") (name "unconnected-(U4-Q7-Pad6)") (class "Default")
      (node (ref "U4") (pin "6") (pinfunction "Q7_6") (pintype "passive"))
    )
    (net (code "73") (name "unconnected-(U4-Q8-Pad14)") (class "Default")
      (node (ref "U4") (pin "14") (pinfunction "Q8_14") (pintype "passive"))
    )
    (net (code "74") (name "unconnected-(U4-Q9-Pad13)") (class "Default")
      (node (ref "U4") (pin "13") (pinfunction "Q9_13") (pintype "passive"))
    )
    (net (code "75") (name "unconnected-(U4-Q10-Pad15)") (class "Default")
      (node (ref "U4") (pin "15") (pinfunction "Q10_15") (pintype "passive"))
    )
    (net (code "76") (name "unconnected-(U4-Q12-Pad1)") (class "Default")
      (node (ref "U4") (pin "1") (pinfunction "Q12_1") (pintype "passive"))
    )
    (net (code "77") (name "unconnected-(U4-Q13-Pad2)") (class "Default")
      (node (ref "U4") (pin "2") (pinfunction "Q13_2") (pintype "passive"))
    )
    (net (code "78") (name "unconnected-(U4-Q14-Pad3)") (class "Default")
      (node (ref "U4") (pin "3") (pinfunction "Q14_3") (pintype "passive"))
    )
  )
)
